# voltage-sensor.net
KiCad netlist of a schematic drawn in EAGLE
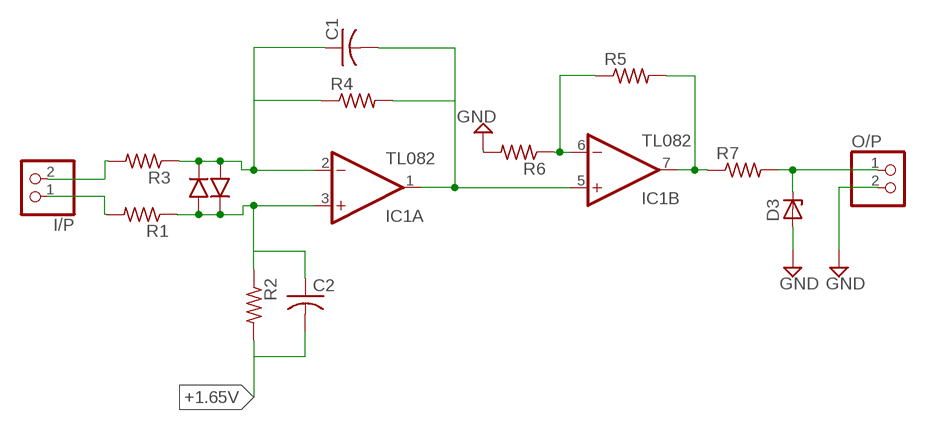
[diagram p0: schematic, sheet 1]

(export (version "E")
  (design (tool "Eeschema 10.0.6"))
  (components
    (comp (ref "C1")
      (value "C-US025-050X050")
      (footprint "eagle-import:C025-050X050")
      (libsource (lib "eagle-import") (part "C-US025-050X050"))
    )
    (comp (ref "C2")
      (value "C-US025-050X050")
      (footprint "eagle-import:C025-050X050")
      (libsource (lib "eagle-import") (part "C-US025-050X050"))
    )
    (comp (ref "D1")
      (value "1N4004")
      (footprint "eagle-import:DO41-10")
      (libsource (lib "eagle-import") (part "1N4004"))
    )
    (comp (ref "D2")
      (value "1N4004")
      (footprint "eagle-import:DO41-10")
      (libsource (lib "eagle-import") (part "1N4004"))
    )
    (comp (ref "D3")
      (value "ZENER-DIODEC1702-15")
      (footprint "eagle-import:C1702-15")
      (libsource (lib "eagle-import") (part "ZENER-DIODEC1702-15"))
    )
    (comp (ref "I/P")
      (value "PINHD-1X2")
      (footprint "eagle-import:1X02")
      (libsource (lib "eagle-import") (part "PINHD-1X2"))
    )
    (comp (ref "IC1")
      (value "TL082")
      (footprint "eagle-import:DIL08")
      (libsource (lib "eagle-import") (part "TL082P"))
    )
    (comp (ref "O/P")
      (value "PINHD-1X2")
      (footprint "eagle-import:1X02")
      (libsource (lib "eagle-import") (part "PINHD-1X2"))
    )
    (comp (ref "R1")
      (value "R-US_0207/10")
      (footprint "eagle-import:0207_10")
      (libsource (lib "eagle-import") (part "R-US_0207/10"))
    )
    (comp (ref "R2")
      (value "R-US_0207/10")
      (footprint "eagle-import:0207_10")
      (libsource (lib "eagle-import") (part "R-US_0207/10"))
    )
    (comp (ref "R3")
      (value "R-US_0207/10")
      (footprint "eagle-import:0207_10")
      (libsource (lib "eagle-import") (part "R-US_0207/10"))
    )
    (comp (ref "R4")
      (value "R-US_0207/10")
      (footprint "eagle-import:0207_10")
      (libsource (lib "eagle-import") (part "R-US_0207/10"))
    )
    (comp (ref "R5")
      (value "R-US_0207/10")
      (footprint "eagle-import:0207_10")
      (libsource (lib "eagle-import") (part "R-US_0207/10"))
    )
    (comp (ref "R6")
      (value "R-US_0207/10")
      (footprint "eagle-import:0207_10")
      (libsource (lib "eagle-import") (part "R-US_0207/10"))
    )
    (comp (ref "R7")
      (value "R-US_0207/10")
      (footprint "eagle-import:0207_10")
      (libsource (lib "eagle-import") (part "R-US_0207/10"))
    )
  )
  (nets
    (net (code "1") (name "+1.65V") (class "Default")
      (node (ref "C2") (pin "2") (pinfunction "2_2") (pintype "passive"))
      (node (ref "R2") (pin "2") (pinfunction "2_2") (pintype "passive"))
    )
    (net (code "2") (name "GND") (class "Default")
      (node (ref "D3") (pin "A") (pinfunction "A_A") (pintype "passive"))
      (node (ref "O/P") (pin "2") (pinfunction "2_2") (pintype "passive"))
      (node (ref "R6") (pin "2") (pinfunction "2_2") (pintype "passive"))
    )
    (net (code "3") (name "Net-(D3-PadC)") (class "Default")
      (node (ref "D3") (pin "C") (pinfunction "C_C") (pintype "passive"))
      (node (ref "O/P") (pin "1") (pinfunction "1_1") (pintype "passive"))
      (node (ref "R7") (pin "2") (pinfunction "2_2") (pintype "passive"))
    )
    (net (code "4") (name "Net-(I/P-Pad1)") (class "Default")
      (node (ref "I/P") (pin "1") (pinfunction "1_1") (pintype "passive"))
      (node (ref "R1") (pin "2") (pinfunction "2_2") (pintype "passive"))
    )
    (net (code "5") (name "Net-(I/P-Pad2)") (class "Default")
      (node (ref "I/P") (pin "2") (pinfunction "2_2") (pintype "passive"))
      (node (ref "R3") (pin "2") (pinfunction "2_2") (pintype "passive"))
    )
    (net (code "6") (name "Net-(IC1A-+IN)") (class "Default")
      (node (ref "C2") (pin "1") (pinfunction "1_1") (pintype "passive"))
      (node (ref "D1") (pin "A") (pinfunction "A_A") (pintype "passive"))
      (node (ref "D2") (pin "C") (pinfunction "C_C") (pintype "passive"))
      (node (ref "IC1") (pin "3") (pinfunction "+IN_3") (pintype "input"))
      (node (ref "R1") (pin "1") (pinfunction "1_1") (pintype "passive"))
      (node (ref "R2") (pin "1") (pinfunction "1_1") (pintype "passive"))
    )
    (net (code "7") (name "Net-(IC1A--IN)") (class "Default")
      (node (ref "C1") (pin "1") (pinfunction "1_1") (pintype "passive"))
      (node (ref "D1") (pin "C") (pinfunction "C_C") (pintype "passive"))
      (node (ref "D2") (pin "A") (pinfunction "A_A") (pintype "passive"))
      (node (ref "IC1") (pin "2") (pinfunction "-IN_2") (pintype "input"))
      (node (ref "R3") (pin "1") (pinfunction "1_1") (pintype "passive"))
      (node (ref "R4") (pin "1") (pinfunction "1_1") (pintype "passive"))
    )
    (net (code "8") (name "Net-(IC1A-OUT)") (class "Default")
      (node (ref "C1") (pin "2") (pinfunction "2_2") (pintype "passive"))
      (node (ref "IC1") (pin "1") (pinfunction "OUT_1") (pintype "output"))
      (node (ref "IC1") (pin "5") (pinfunction "+IN_5") (pintype "input"))
      (node (ref "R4") (pin "2") (pinfunction "2_2") (pintype "passive"))
    )
    (net (code "9") (name "Net-(IC1B--IN)") (class "Default")
      (node (ref "IC1") (pin "6") (pinfunction "-IN_6") (pintype "input"))
      (node (ref "R5") (pin "1") (pinfunction "1_1") (pintype "passive"))
      (node (ref "R6") (pin "1") (pinfunction "1_1") (pintype "passive"))
    )
    (net (code "10") (name "Net-(IC1B-OUT)") (class "Default")
      (node (ref "IC1") (pin "7") (pinfunction "OUT_7") (pintype "output"))
      (node (ref "R5") (pin "2") (pinfunction "2_2") (pintype "passive"))
      (node (ref "R7") (pin "1") (pinfunction "1_1") (pintype "passive"))
    )
  )
)
